# CPU_LPC1776.net
KiCad netlist of a schematic drawn in Altium Designer
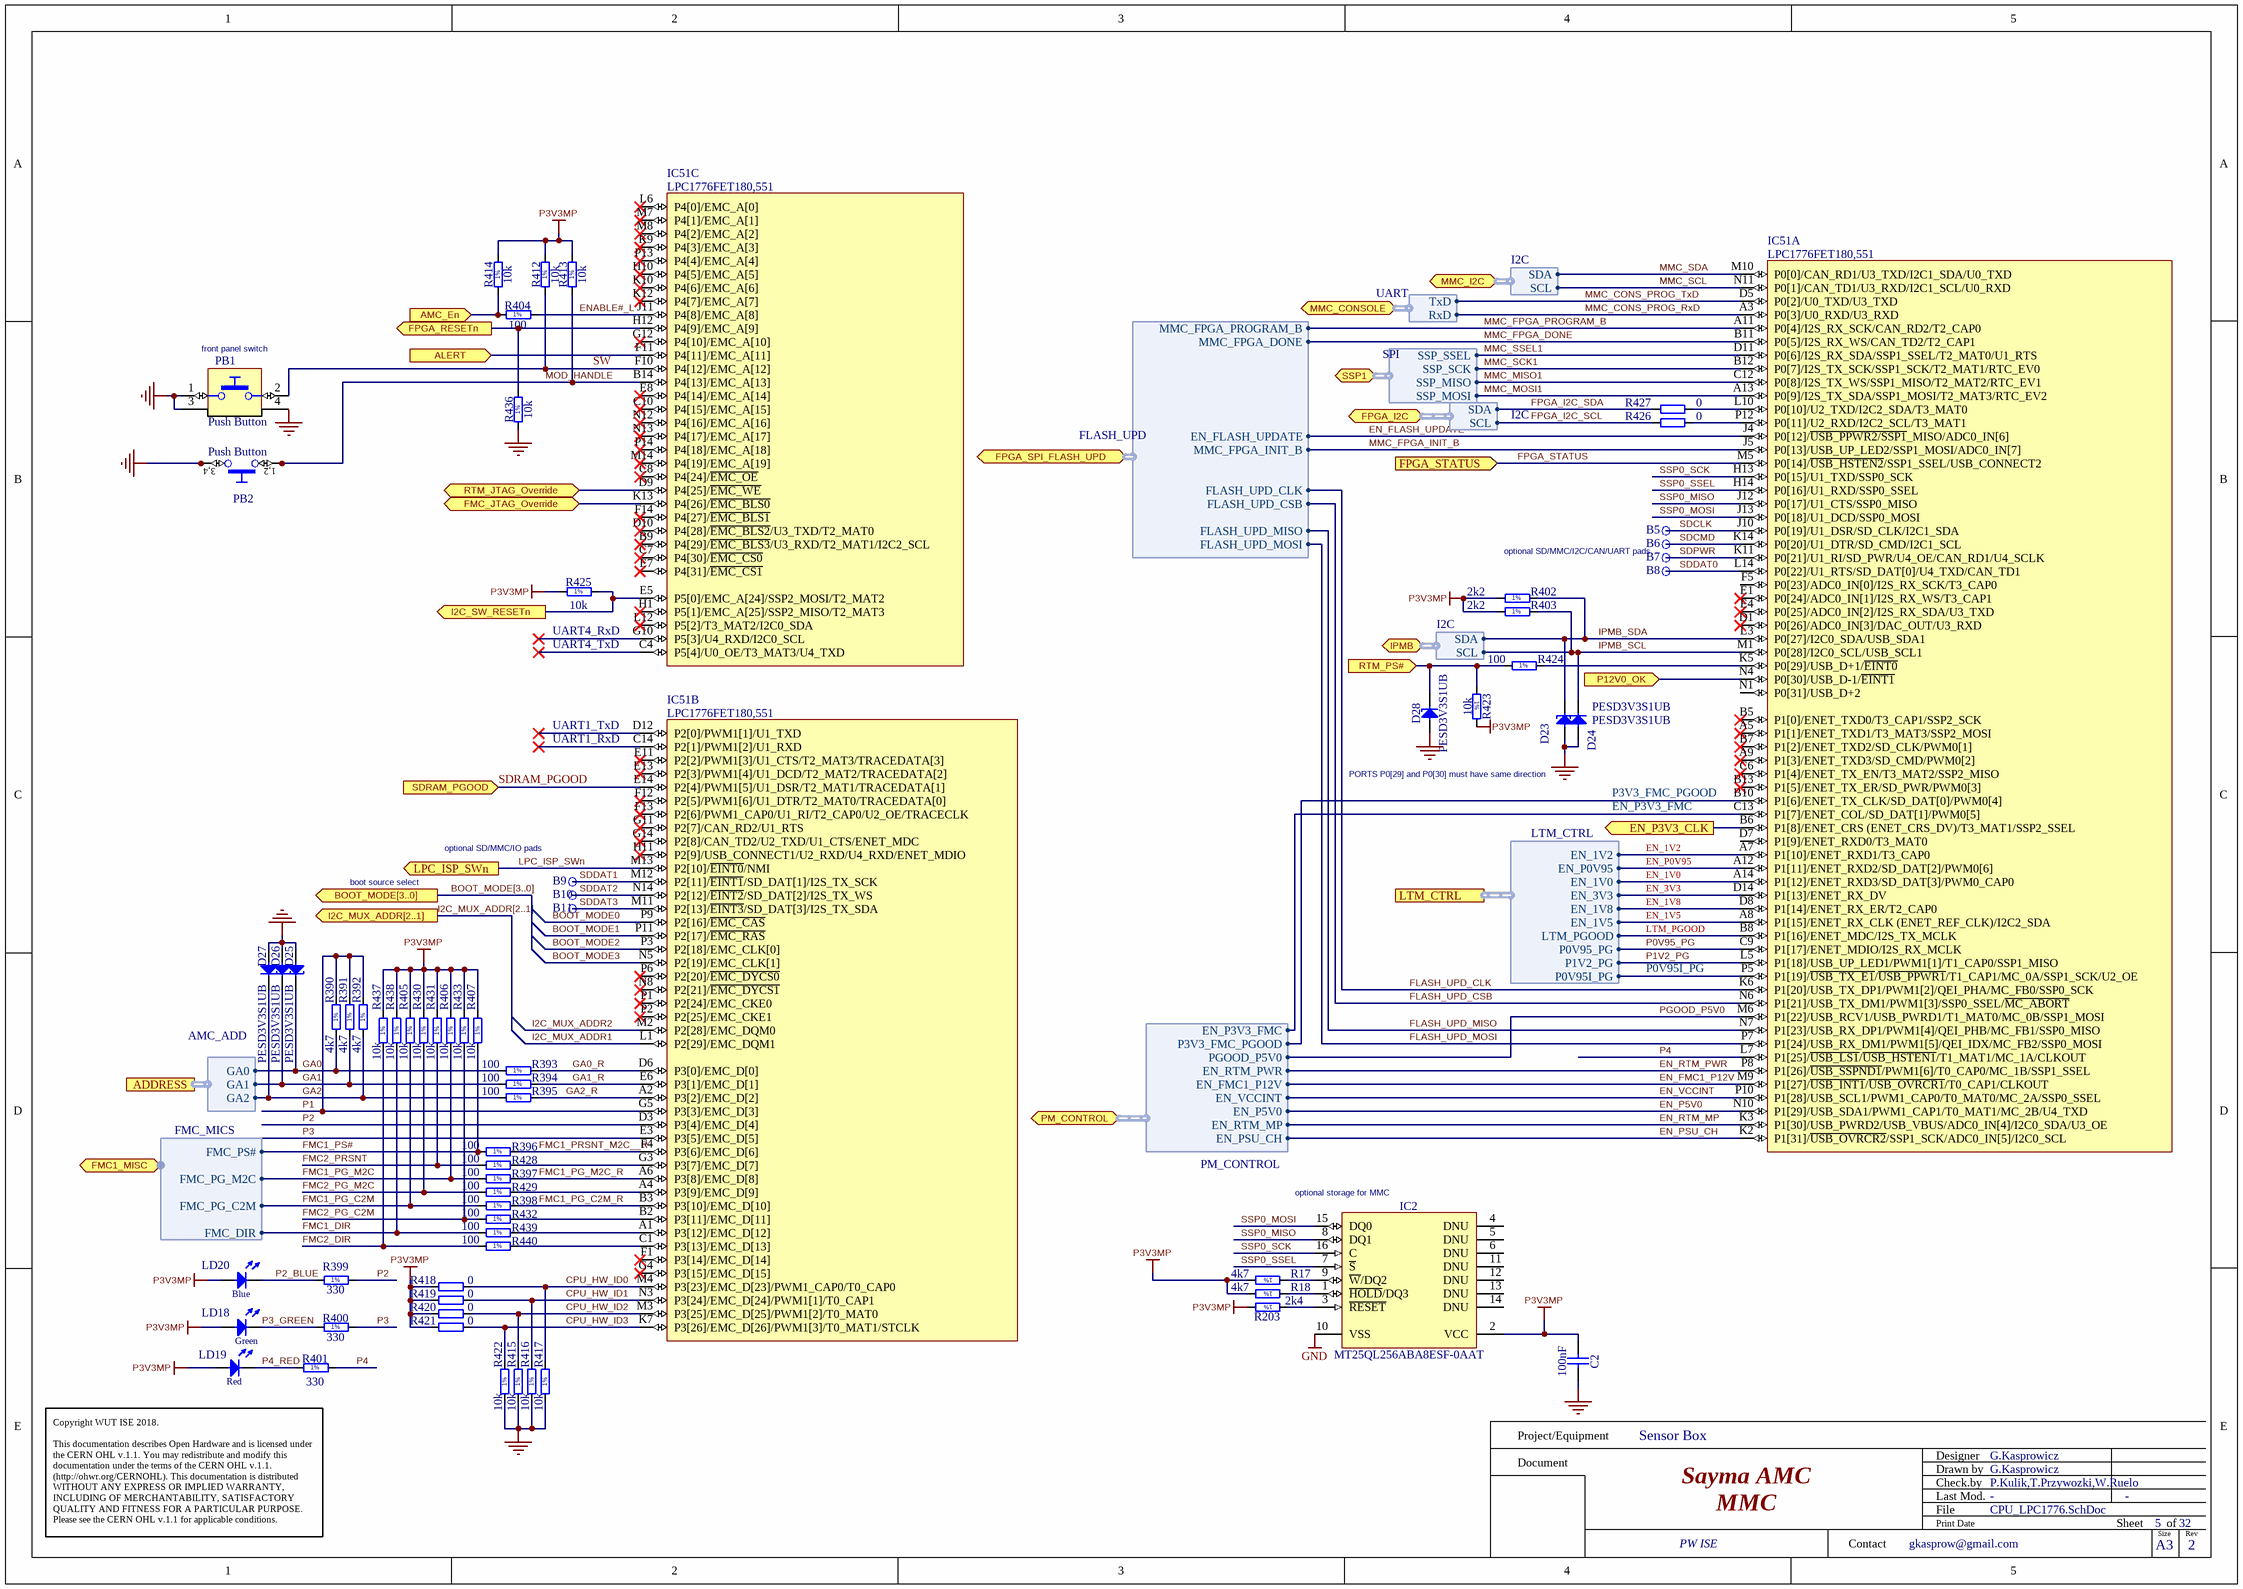
[diagram p0: CPU_LPC1776.SchDoc]

(export (version "E")
  (design (tool "Eeschema 10.0.6"))
  (components
    (comp (ref "B5")
      (value "SMD_PAD_D1MM")
      (footprint "C100")
      (libsource (lib "altium-import") (part "root_0__*"))
    )
    (comp (ref "B6")
      (value "SMD_PAD_D1MM")
      (footprint "C100")
      (libsource (lib "altium-import") (part "root_0__*"))
    )
    (comp (ref "B7")
      (value "SMD_PAD_D1MM")
      (footprint "C100")
      (libsource (lib "altium-import") (part "root_0__*"))
    )
    (comp (ref "B8")
      (value "SMD_PAD_D1MM")
      (footprint "C100")
      (libsource (lib "altium-import") (part "root_0__*"))
    )
    (comp (ref "B9")
      (value "SMD_PAD_D1MM")
      (footprint "C100")
      (libsource (lib "altium-import") (part "root_0__*"))
    )
    (comp (ref "B10")
      (value "SMD_PAD_D1MM")
      (footprint "C100")
      (libsource (lib "altium-import") (part "root_0__*"))
    )
    (comp (ref "B11")
      (value "SMD_PAD_D1MM")
      (footprint "C100")
      (libsource (lib "altium-import") (part "root_0__*"))
    )
    (comp (ref "C2")
      (value "100nF")
      (footprint "CAPC0603X33N")
      (description "Non-polarised capacitor")
      (fields
        (field (name "MANUFACTURER PART NUMBER") "CC0201_100NF_6.3V_10%_X5R")
        (field (name "MANUFACTURER") "GENERIC")
        (field (name "AUTHOR") "CERN DEM JLC")
      )
      (libsource (lib "Capacitors") (part "Capacitor - non polarized"))
    )
    (comp (ref "D23")
      (value "PESD3V3S1UB")
      (footprint "SODFL1608X65N")
      (description "ESD protection diode")
      (fields
        (field (name "MANUFACTURER") "NXP SEMICONDUCTORS")
        (field (name "VOLTAGE") "3V3")
        (field (name "AUTHOR") "CERN DEM JLC")
      )
      (libsource (lib "ICs And Semiconductors") (part "Diode ESD"))
    )
    (comp (ref "D24")
      (value "PESD3V3S1UB")
      (footprint "SODFL1608X65N")
      (description "ESD protection diode")
      (fields
        (field (name "MANUFACTURER") "NXP SEMICONDUCTORS")
        (field (name "VOLTAGE") "3V3")
        (field (name "AUTHOR") "CERN DEM JLC")
      )
      (libsource (lib "ICs And Semiconductors") (part "Diode ESD"))
    )
    (comp (ref "D25")
      (value "PESD3V3S1UB")
      (footprint "SODFL1608X65N")
      (description "ESD protection diode")
      (fields
        (field (name "MANUFACTURER") "NXP SEMICONDUCTORS")
        (field (name "VOLTAGE") "3V3")
        (field (name "AUTHOR") "CERN DEM JLC")
      )
      (libsource (lib "ICs And Semiconductors") (part "Diode ESD"))
    )
    (comp (ref "D26")
      (value "PESD3V3S1UB")
      (footprint "SODFL1608X65N")
      (description "ESD protection diode")
      (fields
        (field (name "MANUFACTURER") "NXP SEMICONDUCTORS")
        (field (name "VOLTAGE") "3V3")
        (field (name "AUTHOR") "CERN DEM JLC")
      )
      (libsource (lib "ICs And Semiconductors") (part "Diode ESD"))
    )
    (comp (ref "D27")
      (value "PESD3V3S1UB")
      (footprint "SODFL1608X65N")
      (description "ESD protection diode")
      (fields
        (field (name "MANUFACTURER") "NXP SEMICONDUCTORS")
        (field (name "VOLTAGE") "3V3")
        (field (name "AUTHOR") "CERN DEM JLC")
      )
      (libsource (lib "ICs And Semiconductors") (part "Diode ESD"))
    )
    (comp (ref "D28")
      (value "PESD3V3S1UB")
      (footprint "SODFL1608X65N")
      (description "ESD protection diode")
      (fields
        (field (name "MANUFACTURER") "NXP SEMICONDUCTORS")
        (field (name "VOLTAGE") "3V3")
        (field (name "AUTHOR") "CERN DEM JLC")
      )
      (libsource (lib "ICs And Semiconductors") (part "Diode ESD"))
    )
    (comp (ref "IC2")
      (value "MT25QL256ABA8ESF-0AAT")
      (footprint "SOIC127P1030X265-16N")
      (description "256Mbit (32MB), 2.7V-3.6V, Multiple I/O Serial NOR Flash Memory,with Reset# & Hold#")
      (fields (field (name "MANUFACTURER") "MICRON TECHNOLOGY") (field (name "AUTHOR") "CERN DEM JLC"))
      (libsource (lib "ICs And Semiconductors") (part "MT25QL256ABA8ESF"))
    )
    (comp (ref "IC51")
      (value "LPC1776FET180,551")
      (footprint "BGA180C80P14X14_1200X1200X120")
      (fields (field (name "MANUFACTURER") "NXP SEMICONDUCTORS") (field (name "AUTHOR") "CERN DEM JMW"))
      (libsource (lib "ICs And Semiconductors") (part "LPC1776FET180,551"))
    )
    (comp (ref "LD18")
      (value "Green")
      (footprint "LED_AVAGO_HSME-C120")
      (description "LED Green 1C 2A")
      (fields
        (field (name "MANUFACTURER PART NUMBER") "HSME-C120")
        (field (name "MANUFACTURER") "AVAGO TECHNOLOGIES")
        (field (name "AUTHOR") "CERN DEM JMW")
      )
      (libsource (lib "ICs And Semiconductors") (part "LED Green 1C 2A"))
    )
    (comp (ref "LD19")
      (value "Red")
      (footprint "LED_KINGBRIGHT_KPH-1608SURCK")
      (description "LED Red 1C 2A")
      (fields
        (field (name "PART NUMBER") "LED_KINGBRIGHT_KPH-1608SURCK")
        (field (name "MANUFACTURER") "KINGBRIGHT")
        (field (name "AUTHOR") "CERN DEM JLC")
      )
      (libsource (lib "ICs And Semiconductors") (part "LED Red 1C 2A"))
    )
    (comp (ref "LD20")
      (value "Blue")
      (footprint "LED_AVAGO_HSMR-C120")
      (description "LED Blue 1C 2A")
      (fields
        (field (name "MANUFACTURER PART NUMBER") "HSMR-C120")
        (field (name "MANUFACTURER") "AVAGO TECHNOLOGIES")
        (field (name "AUTHOR") "CERN DEM JLC")
      )
      (libsource (lib "ICs And Semiconductors") (part "LED Blue 1C 2A"))
    )
    (comp (ref "PB1")
      (value "Push Button")
      (footprint "PB_ALPS_SKHHLQA010")
      (description "Push-Button Switch SPDT")
      (fields
        (field (name "MANUFACTURER PART NUMBER") "SKHHLQA010")
        (field (name "MANUFACTURER") "ALPS")
        (field (name "AUTHOR") "CERN DEM JLC")
      )
      (libsource (lib "Eletro-mechanical") (part "PB SPST 1NO-2NO 34CASE"))
    )
    (comp (ref "PB2")
      (value "Push Button")
      (footprint "SW_C&K_HDT0001")
      (description "Push-Button Switch SPDT")
      (fields
        (field (name "MANUFACTURER PART NUMBER") "HDT0001")
        (field (name "MANUFACTURER") "C&K")
        (field (name "AUTHOR") "CERN DEM JLC")
      )
      (libsource (lib "Eletro-mechanical") (part "PB SPST 12NO-34NO"))
    )
    (comp (ref "R17")
      (value "4k7")
      (footprint "RESC1005X40N")
      (description "Resistor - 1%")
      (fields
        (field (name "MANUFACTURER PART NUMBER") "R0402_4K7_1%_0.0625W_100PPM")
        (field (name "MANUFACTURER") "GENERIC")
        (field (name "AUTHOR") "CERN DEM JLC")
      )
      (libsource (lib "Resistors") (part "Resistor - 1%"))
    )
    (comp (ref "R18")
      (value "4k7")
      (footprint "RESC1005X40N")
      (description "Resistor - 1%")
      (fields
        (field (name "MANUFACTURER PART NUMBER") "R0402_4K7_1%_0.0625W_100PPM")
        (field (name "MANUFACTURER") "GENERIC")
        (field (name "AUTHOR") "CERN DEM JLC")
      )
      (libsource (lib "Resistors") (part "Resistor - 1%"))
    )
    (comp (ref "R203")
      (value "2k4")
      (footprint "RESC1005X40N")
      (description "Resistor - 1%")
      (fields
        (field (name "MANUFACTURER PART NUMBER") "R0402_2K4_1%_0.0625W_100PPM")
        (field (name "MANUFACTURER") "GENERIC")
        (field (name "AUTHOR") "CERN DEM JLC")
      )
      (libsource (lib "Resistors") (part "Resistor - 1%"))
    )
    (comp (ref "R390")
      (value "4k7")
      (footprint "RESC1005X40N")
      (description "Resistor - 1%")
      (fields
        (field (name "MANUFACTURER PART NUMBER") "R0402_4K7_1%_0.0625W_100PPM")
        (field (name "MANUFACTURER") "GENERIC")
        (field (name "AUTHOR") "CERN DEM JLC")
      )
      (libsource (lib "Resistors") (part "Resistor - 1%"))
    )
    (comp (ref "R391")
      (value "4k7")
      (footprint "RESC1005X40N")
      (description "Resistor - 1%")
      (fields
        (field (name "MANUFACTURER PART NUMBER") "R0402_4K7_1%_0.0625W_100PPM")
        (field (name "MANUFACTURER") "GENERIC")
        (field (name "AUTHOR") "CERN DEM JLC")
      )
      (libsource (lib "Resistors") (part "Resistor - 1%"))
    )
    (comp (ref "R392")
      (value "4k7")
      (footprint "RESC1005X40N")
      (description "Resistor - 1%")
      (fields
        (field (name "MANUFACTURER PART NUMBER") "R0402_4K7_1%_0.0625W_100PPM")
        (field (name "MANUFACTURER") "GENERIC")
        (field (name "AUTHOR") "CERN DEM JLC")
      )
      (libsource (lib "Resistors") (part "Resistor - 1%"))
    )
    (comp (ref "R393")
      (value "100")
      (footprint "RESC1005X40N")
      (description "Resistor - 1%")
      (fields
        (field (name "MANUFACTURER PART NUMBER") "R0402_100R_1%_0.1W_100PPM_50V")
        (field (name "MANUFACTURER") "GENERIC")
        (field (name "AUTHOR") "CERN DEM JLC")
      )
      (libsource (lib "Resistors") (part "Resistor - 1%"))
    )
    (comp (ref "R394")
      (value "100")
      (footprint "RESC1005X40N")
      (description "Resistor - 1%")
      (fields
        (field (name "MANUFACTURER PART NUMBER") "R0402_100R_1%_0.1W_100PPM_50V")
        (field (name "MANUFACTURER") "GENERIC")
        (field (name "AUTHOR") "CERN DEM JLC")
      )
      (libsource (lib "Resistors") (part "Resistor - 1%"))
    )
    (comp (ref "R395")
      (value "100")
      (footprint "RESC1005X40N")
      (description "Resistor - 1%")
      (fields
        (field (name "MANUFACTURER PART NUMBER") "R0402_100R_1%_0.1W_100PPM_50V")
        (field (name "MANUFACTURER") "GENERIC")
        (field (name "AUTHOR") "CERN DEM JLC")
      )
      (libsource (lib "Resistors") (part "Resistor - 1%"))
    )
    (comp (ref "R396")
      (value "100")
      (footprint "RESC1005X40N")
      (description "Resistor - 1%")
      (fields
        (field (name "MANUFACTURER PART NUMBER") "R0402_100R_1%_0.1W_100PPM_50V")
        (field (name "MANUFACTURER") "GENERIC")
        (field (name "AUTHOR") "CERN DEM JLC")
      )
      (libsource (lib "Resistors") (part "Resistor - 1%"))
    )
    (comp (ref "R397")
      (value "100")
      (footprint "RESC1005X40N")
      (description "Resistor - 1%")
      (fields
        (field (name "MANUFACTURER PART NUMBER") "R0402_100R_1%_0.1W_100PPM_50V")
        (field (name "MANUFACTURER") "GENERIC")
        (field (name "AUTHOR") "CERN DEM JLC")
      )
      (libsource (lib "Resistors") (part "Resistor - 1%"))
    )
    (comp (ref "R398")
      (value "100")
      (footprint "RESC1005X40N")
      (description "Resistor - 1%")
      (fields
        (field (name "MANUFACTURER PART NUMBER") "R0402_100R_1%_0.1W_100PPM_50V")
        (field (name "MANUFACTURER") "GENERIC")
        (field (name "AUTHOR") "CERN DEM JLC")
      )
      (libsource (lib "Resistors") (part "Resistor - 1%"))
    )
    (comp (ref "R399")
      (value "330")
      (footprint "RESC1005X40N")
      (description "Resistor - 1%")
      (fields
        (field (name "MANUFACTURER PART NUMBER") "R0402_330R_1%_0.0625W_100PPM")
        (field (name "MANUFACTURER") "GENERIC")
        (field (name "AUTHOR") "CERN DEM JLC")
      )
      (libsource (lib "Resistors") (part "Resistor - 1%"))
    )
    (comp (ref "R400")
      (value "330")
      (footprint "RESC1005X40N")
      (description "Resistor - 1%")
      (fields
        (field (name "MANUFACTURER PART NUMBER") "R0402_330R_1%_0.0625W_100PPM")
        (field (name "MANUFACTURER") "GENERIC")
        (field (name "AUTHOR") "CERN DEM JLC")
      )
      (libsource (lib "Resistors") (part "Resistor - 1%"))
    )
    (comp (ref "R401")
      (value "330")
      (footprint "RESC1005X40N")
      (description "Resistor - 1%")
      (fields
        (field (name "MANUFACTURER PART NUMBER") "R0402_330R_1%_0.0625W_100PPM")
        (field (name "MANUFACTURER") "GENERIC")
        (field (name "AUTHOR") "CERN DEM JLC")
      )
      (libsource (lib "Resistors") (part "Resistor - 1%"))
    )
    (comp (ref "R402")
      (value "2k2")
      (footprint "RESC1005X40N")
      (description "Resistor - 1%")
      (fields
        (field (name "MANUFACTURER PART NUMBER") "R0402_2K2_1%_0.0625W_100PPM")
        (field (name "MANUFACTURER") "GENERIC")
        (field (name "AUTHOR") "CERN DEM JLC")
      )
      (libsource (lib "Resistors") (part "Resistor - 1%"))
    )
    (comp (ref "R403")
      (value "2k2")
      (footprint "RESC1005X40N")
      (description "Resistor - 1%")
      (fields
        (field (name "MANUFACTURER PART NUMBER") "R0402_2K2_1%_0.0625W_100PPM")
        (field (name "MANUFACTURER") "GENERIC")
        (field (name "AUTHOR") "CERN DEM JLC")
      )
      (libsource (lib "Resistors") (part "Resistor - 1%"))
    )
    (comp (ref "R404")
      (value "100")
      (footprint "RESC1005X40N")
      (description "Resistor - 1%")
      (fields
        (field (name "MANUFACTURER PART NUMBER") "R0402_100R_1%_0.1W_100PPM_50V")
        (field (name "MANUFACTURER") "GENERIC")
        (field (name "AUTHOR") "CERN DEM JLC")
      )
      (libsource (lib "Resistors") (part "Resistor - 1%"))
    )
    (comp (ref "R405")
      (value "10k")
      (footprint "RESC1005X40N")
      (description "Resistor - 1%")
      (fields
        (field (name "MANUFACTURER PART NUMBER") "R0402_10K_1%_0.0625W_100PPM")
        (field (name "MANUFACTURER") "GENERIC")
        (field (name "AUTHOR") "CERN DEM JLC")
      )
      (libsource (lib "Resistors") (part "Resistor - 1%"))
    )
    (comp (ref "R406")
      (value "10k")
      (footprint "RESC1005X40N")
      (description "Resistor - 1%")
      (fields
        (field (name "MANUFACTURER PART NUMBER") "R0402_10K_1%_0.0625W_100PPM")
        (field (name "MANUFACTURER") "GENERIC")
        (field (name "AUTHOR") "CERN DEM JLC")
      )
      (libsource (lib "Resistors") (part "Resistor - 1%"))
    )
    (comp (ref "R407")
      (value "10k")
      (footprint "RESC1005X40N")
      (description "Resistor - 1%")
      (fields
        (field (name "MANUFACTURER PART NUMBER") "R0402_10K_1%_0.0625W_100PPM")
        (field (name "MANUFACTURER") "GENERIC")
        (field (name "AUTHOR") "CERN DEM JLC")
      )
      (libsource (lib "Resistors") (part "Resistor - 1%"))
    )
    (comp (ref "R412")
      (value "10k")
      (footprint "RESC1005X40N")
      (description "Resistor - 1%")
      (fields
        (field (name "MANUFACTURER PART NUMBER") "R0402_10K_1%_0.0625W_100PPM")
        (field (name "MANUFACTURER") "GENERIC")
        (field (name "AUTHOR") "CERN DEM JLC")
      )
      (libsource (lib "Resistors") (part "Resistor - 1%"))
    )
    (comp (ref "R413")
      (value "10k")
      (footprint "RESC1005X40N")
      (description "Resistor - 1%")
      (fields
        (field (name "MANUFACTURER PART NUMBER") "R0402_10K_1%_0.0625W_100PPM")
        (field (name "MANUFACTURER") "GENERIC")
        (field (name "AUTHOR") "CERN DEM JLC")
      )
      (libsource (lib "Resistors") (part "Resistor - 1%"))
    )
    (comp (ref "R414")
      (value "10k")
      (footprint "RESC1005X40N")
      (description "Resistor - 1%")
      (fields
        (field (name "MANUFACTURER PART NUMBER") "R0402_10K_1%_0.0625W_100PPM")
        (field (name "MANUFACTURER") "GENERIC")
        (field (name "AUTHOR") "CERN DEM JLC")
      )
      (libsource (lib "Resistors") (part "Resistor - 1%"))
    )
    (comp (ref "R415")
      (value "10k")
      (footprint "RESC1005X40N")
      (description "Resistor - 1%")
      (fields
        (field (name "MANUFACTURER PART NUMBER") "R0402_10K_1%_0.0625W_100PPM")
        (field (name "MANUFACTURER") "GENERIC")
        (field (name "AUTHOR") "CERN DEM JLC")
      )
      (libsource (lib "Resistors") (part "Resistor - 1%"))
    )
    (comp (ref "R416")
      (value "10k")
      (footprint "RESC1005X40N")
      (description "Resistor - 1%")
      (fields
        (field (name "MANUFACTURER PART NUMBER") "R0402_10K_1%_0.0625W_100PPM")
        (field (name "MANUFACTURER") "GENERIC")
        (field (name "AUTHOR") "CERN DEM JLC")
      )
      (libsource (lib "Resistors") (part "Resistor - 1%"))
    )
    (comp (ref "R417")
      (value "10k")
      (footprint "RESC1005X40N")
      (description "Resistor - 1%")
      (fields
        (field (name "MANUFACTURER PART NUMBER") "R0402_10K_1%_0.0625W_100PPM")
        (field (name "MANUFACTURER") "GENERIC")
        (field (name "AUTHOR") "CERN DEM JLC")
      )
      (libsource (lib "Resistors") (part "Resistor - 1%"))
    )
    (comp (ref "R418")
      (value "0")
      (footprint "RESC1005X40N")
      (description "Resistor")
      (fields
        (field (name "MANUFACTURER PART NUMBER") "R0402_0R_JUMPER")
        (field (name "MANUFACTURER") "GENERIC")
        (field (name "AUTHOR") "CERN DEM JLC")
      )
      (libsource (lib "Resistors") (part "Resistor"))
    )
    (comp (ref "R419")
      (value "0")
      (footprint "RESC1005X40N")
      (description "Resistor")
      (fields
        (field (name "MANUFACTURER PART NUMBER") "R0402_0R_JUMPER")
        (field (name "MANUFACTURER") "GENERIC")
        (field (name "AUTHOR") "CERN DEM JLC")
      )
      (libsource (lib "Resistors") (part "Resistor"))
    )
    (comp (ref "R420")
      (value "0")
      (footprint "RESC1005X40N")
      (description "Resistor")
      (fields
        (field (name "MANUFACTURER PART NUMBER") "R0402_0R_JUMPER")
        (field (name "MANUFACTURER") "GENERIC")
        (field (name "AUTHOR") "CERN DEM JLC")
      )
      (libsource (lib "Resistors") (part "Resistor"))
    )
    (comp (ref "R421")
      (value "0")
      (footprint "RESC1005X40N")
      (description "Resistor")
      (fields
        (field (name "MANUFACTURER PART NUMBER") "R0402_0R_JUMPER")
        (field (name "MANUFACTURER") "GENERIC")
        (field (name "AUTHOR") "CERN DEM JLC")
      )
      (libsource (lib "Resistors") (part "Resistor"))
    )
    (comp (ref "R422")
      (value "10k")
      (footprint "RESC1005X40N")
      (description "Resistor - 1%")
      (fields
        (field (name "MANUFACTURER PART NUMBER") "R0402_10K_1%_0.0625W_100PPM")
        (field (name "MANUFACTURER") "GENERIC")
        (field (name "AUTHOR") "CERN DEM JLC")
      )
      (libsource (lib "Resistors") (part "Resistor - 1%"))
    )
    (comp (ref "R423")
      (value "10k")
      (footprint "RESC1005X40N")
      (description "Resistor - 1%")
      (fields
        (field (name "MANUFACTURER PART NUMBER") "R0402_10K_1%_0.0625W_100PPM")
        (field (name "MANUFACTURER") "GENERIC")
        (field (name "AUTHOR") "CERN DEM JLC")
      )
      (libsource (lib "Resistors") (part "Resistor - 1%"))
    )
    (comp (ref "R424")
      (value "100")
      (footprint "RESC1005X40N")
      (description "Resistor - 1%")
      (fields
        (field (name "MANUFACTURER PART NUMBER") "R0402_100R_1%_0.1W_100PPM_50V")
        (field (name "MANUFACTURER") "GENERIC")
        (field (name "AUTHOR") "CERN DEM JLC")
      )
      (libsource (lib "Resistors") (part "Resistor - 1%"))
    )
    (comp (ref "R425")
      (value "10k")
      (footprint "RESC1005X40N")
      (description "Resistor - 1%")
      (fields
        (field (name "MANUFACTURER PART NUMBER") "R0402_10K_1%_0.0625W_100PPM")
        (field (name "MANUFACTURER") "GENERIC")
        (field (name "AUTHOR") "CERN DEM JLC")
      )
      (libsource (lib "Resistors") (part "Resistor - 1%"))
    )
    (comp (ref "R426")
      (value "0")
      (footprint "RESC1005X40N")
      (description "Resistor")
      (fields
        (field (name "MANUFACTURER PART NUMBER") "R0402_0R_JUMPER")
        (field (name "MANUFACTURER") "GENERIC")
        (field (name "AUTHOR") "CERN DEM JLC")
      )
      (libsource (lib "Resistors") (part "Resistor"))
    )
    (comp (ref "R427")
      (value "0")
      (footprint "RESC1005X40N")
      (description "Resistor")
      (fields
        (field (name "MANUFACTURER PART NUMBER") "R0402_0R_JUMPER")
        (field (name "MANUFACTURER") "GENERIC")
        (field (name "AUTHOR") "CERN DEM JLC")
      )
      (libsource (lib "Resistors") (part "Resistor"))
    )
    (comp (ref "R428")
      (value "100")
      (footprint "RESC1005X40N")
      (description "Resistor - 1%")
      (fields
        (field (name "MANUFACTURER PART NUMBER") "R0402_100R_1%_0.1W_100PPM_50V")
        (field (name "MANUFACTURER") "GENERIC")
        (field (name "AUTHOR") "CERN DEM JLC")
      )
      (libsource (lib "Resistors") (part "Resistor - 1%"))
    )
    (comp (ref "R429")
      (value "100")
      (footprint "RESC1005X40N")
      (description "Resistor - 1%")
      (fields
        (field (name "MANUFACTURER PART NUMBER") "R0402_100R_1%_0.1W_100PPM_50V")
        (field (name "MANUFACTURER") "GENERIC")
        (field (name "AUTHOR") "CERN DEM JLC")
      )
      (libsource (lib "Resistors") (part "Resistor - 1%"))
    )
    (comp (ref "R430")
      (value "10k")
      (footprint "RESC1005X40N")
      (description "Resistor - 1%")
      (fields
        (field (name "MANUFACTURER PART NUMBER") "R0402_10K_1%_0.0625W_100PPM")
        (field (name "MANUFACTURER") "GENERIC")
        (field (name "AUTHOR") "CERN DEM JLC")
      )
      (libsource (lib "Resistors") (part "Resistor - 1%"))
    )
    (comp (ref "R431")
      (value "10k")
      (footprint "RESC1005X40N")
      (description "Resistor - 1%")
      (fields
        (field (name "MANUFACTURER PART NUMBER") "R0402_10K_1%_0.0625W_100PPM")
        (field (name "MANUFACTURER") "GENERIC")
        (field (name "AUTHOR") "CERN DEM JLC")
      )
      (libsource (lib "Resistors") (part "Resistor - 1%"))
    )
    (comp (ref "R432")
      (value "100")
      (footprint "RESC1005X40N")
      (description "Resistor - 1%")
      (fields
        (field (name "MANUFACTURER PART NUMBER") "R0402_100R_1%_0.1W_100PPM_50V")
        (field (name "MANUFACTURER") "GENERIC")
        (field (name "AUTHOR") "CERN DEM JLC")
      )
      (libsource (lib "Resistors") (part "Resistor - 1%"))
    )
    (comp (ref "R433")
      (value "10k")
      (footprint "RESC1005X40N")
      (description "Resistor - 1%")
      (fields
        (field (name "MANUFACTURER PART NUMBER") "R0402_10K_1%_0.0625W_100PPM")
        (field (name "MANUFACTURER") "GENERIC")
        (field (name "AUTHOR") "CERN DEM JLC")
      )
      (libsource (lib "Resistors") (part "Resistor - 1%"))
    )
    (comp (ref "R436")
      (value "10k")
      (footprint "RESC1005X40N")
      (description "Resistor - 1%")
      (fields
        (field (name "MANUFACTURER PART NUMBER") "R0402_10K_1%_0.0625W_100PPM")
        (field (name "MANUFACTURER") "GENERIC")
        (field (name "AUTHOR") "CERN DEM JLC")
      )
      (libsource (lib "Resistors") (part "Resistor - 1%"))
    )
    (comp (ref "R437")
      (value "10k")
      (footprint "RESC1005X40N")
      (description "Resistor - 1%")
      (fields
        (field (name "MANUFACTURER PART NUMBER") "R0402_10K_1%_0.0625W_100PPM")
        (field (name "MANUFACTURER") "GENERIC")
        (field (name "AUTHOR") "CERN DEM JLC")
      )
      (libsource (lib "Resistors") (part "Resistor - 1%"))
    )
    (comp (ref "R438")
      (value "10k")
      (footprint "RESC1005X40N")
      (description "Resistor - 1%")
      (fields
        (field (name "MANUFACTURER PART NUMBER") "R0402_10K_1%_0.0625W_100PPM")
        (field (name "MANUFACTURER") "GENERIC")
        (field (name "AUTHOR") "CERN DEM JLC")
      )
      (libsource (lib "Resistors") (part "Resistor - 1%"))
    )
    (comp (ref "R439")
      (value "100")
      (footprint "RESC1005X40N")
      (description "Resistor - 1%")
      (fields
        (field (name "MANUFACTURER PART NUMBER") "R0402_100R_1%_0.1W_100PPM_50V")
        (field (name "MANUFACTURER") "GENERIC")
        (field (name "AUTHOR") "CERN DEM JLC")
      )
      (libsource (lib "Resistors") (part "Resistor - 1%"))
    )
    (comp (ref "R440")
      (value "100")
      (footprint "RESC1005X40N")
      (description "Resistor - 1%")
      (fields
        (field (name "MANUFACTURER PART NUMBER") "R0402_100R_1%_0.1W_100PPM_50V")
        (field (name "MANUFACTURER") "GENERIC")
        (field (name "AUTHOR") "CERN DEM JLC")
      )
      (libsource (lib "Resistors") (part "Resistor - 1%"))
    )
  )
  (nets
    (net (code "9") (name "/ALERT") (class "Default")
      (node (ref "IC51") (pin "F11") (pinfunction "P4[11]/EMC_A[11]_F11") (pintype "bidirectional"))
    )
    (net (code "10") (name "/AMC_En") (class "Default")
      (node (ref "R404") (pin "1") (pinfunction "1_1") (pintype "passive"))
      (node (ref "R414") (pin "1") (pinfunction "1_1") (pintype "passive"))
    )
    (net (code "11") (name "/BOOT_MODE0") (class "Default")
      (node (ref "IC51") (pin "P9") (pinfunction "P2[16]/~{EMC_CAS}_P9") (pintype "bidirectional"))
    )
    (net (code "12") (name "/BOOT_MODE1") (class "Default")
      (node (ref "IC51") (pin "P11") (pinfunction "P2[17]/~{EMC_RAS}_P11") (pintype "bidirectional"))
    )
    (net (code "13") (name "/BOOT_MODE2") (class "Default")
      (node (ref "IC51") (pin "P3") (pinfunction "P2[18]/EMC_CLK[0]_P3") (pintype "bidirectional"))
    )
    (net (code "14") (name "/BOOT_MODE3") (class "Default")
      (node (ref "IC51") (pin "N5") (pinfunction "P2[19]/EMC_CLK[1]_N5") (pintype "bidirectional"))
    )
    (net (code "16") (name "/CPU_HW_ID0") (class "Default")
      (node (ref "IC51") (pin "M4") (pinfunction "P3[23]/EMC_D[23]/PWM1_CAP0/T0_CAP0_M4") (pintype "bidirectional"))
      (node (ref "R417") (pin "2") (pinfunction "2_2") (pintype "passive"))
      (node (ref "R418") (pin "2") (pinfunction "2_2") (pintype "passive"))
    )
    (net (code "17") (name "/CPU_HW_ID1") (class "Default")
      (node (ref "IC51") (pin "N3") (pinfunction "P3[24]/EMC_D[24]/PWM1[1]/T0_CAP1_N3") (pintype "bidirectional"))
      (node (ref "R416") (pin "2") (pinfunction "2_2") (pintype "passive"))
      (node (ref "R419") (pin "2") (pinfunction "2_2") (pintype "passive"))
    )
    (net (code "18") (name "/CPU_HW_ID2") (class "Default")
      (node (ref "IC51") (pin "M3") (pinfunction "P3[25]/EMC_D[25]/PWM1[2]/T0_MAT0_M3") (pintype "bidirectional"))
      (node (ref "R415") (pin "2") (pinfunction "2_2") (pintype "passive"))
      (node (ref "R420") (pin "2") (pinfunction "2_2") (pintype "passive"))
    )
    (net (code "19") (name "/CPU_HW_ID3") (class "Default")
      (node (ref "IC51") (pin "K7") (pinfunction "P3[26]/EMC_D[26]/PWM1[3]/T0_MAT1/STCLK_K7") (pintype "bidirectional"))
      (node (ref "R421") (pin "2") (pinfunction "2_2") (pintype "passive"))
      (node (ref "R422") (pin "2") (pinfunction "2_2") (pintype "passive"))
    )
    (net (code "20") (name "/ENABLE#_L") (class "Default")
      (node (ref "IC51") (pin "J11") (pinfunction "P4[8]/EMC_A[8]_J11") (pintype "bidirectional"))
      (node (ref "R404") (pin "2") (pinfunction "2_2") (pintype "passive"))
    )
    (net (code "21") (name "/EN_1V0") (class "Default")
      (node (ref "IC51") (pin "A14") (pinfunction "P1[12]/ENET_RXD3/SD_DAT[3]/PWM0_CAP0_A14") (pintype "bidirectional"))
    )
    (net (code "22") (name "/EN_1V2") (class "Default")
      (node (ref "IC51") (pin "A7") (pinfunction "P1[10]/ENET_RXD1/T3_CAP0_A7") (pintype "bidirectional"))
    )
    (net (code "23") (name "/EN_1V5") (class "Default")
      (node (ref "IC51") (pin "A8") (pinfunction "P1[15]/ENET_RX_CLK_(ENET_REF_CLK)/I2C2_SDA_A8") (pintype "bidirectional"))
    )
    (net (code "24") (name "/EN_1V8") (class "Default")
      (node (ref "IC51") (pin "D8") (pinfunction "P1[14]/ENET_RX_ER/T2_CAP0_D8") (pintype "bidirectional"))
    )
    (net (code "25") (name "/EN_3V3") (class "Default")
      (node (ref "IC51") (pin "D14") (pinfunction "P1[13]/ENET_RX_DV_D14") (pintype "bidirectional"))
    )
    (net (code "26") (name "/EN_FLASH_UPDATE") (class "Default")
      (node (ref "IC51") (pin "J4") (pinfunction "P0[12]/~{USB_PPWR2/SSP1}_MISO/ADC0_IN[6]_J4") (pintype "bidirectional"))
    )
    (net (code "27") (name "/EN_FMC1_P12V") (class "Default")
      (node (ref "IC51") (pin "M9") (pinfunction "P1[27]/~{USB_INT1}/~{USB_OVRCR1}/T0_CAP1/CLKOUT_M9") (pintype "bidirectional"))
    )
    (net (code "28") (name "/EN_P0V95") (class "Default")
      (node (ref "IC51") (pin "A12") (pinfunction "P1[11]/ENET_RXD2/SD_DAT[2]/PWM0[6]_A12") (pintype "bidirectional"))
    )
    (net (code "29") (name "/EN_P3V3_CLK") (class "Default")
      (node (ref "IC51") (pin "B6") (pinfunction "P1[8]/ENET_CRS_(ENET_CRS_DV)/T3_MAT1/SSP2_SSEL_B6") (pintype "bidirectional"))
    )
    (net (code "30") (name "/EN_P3V3_FMC") (class "Default")
      (node (ref "IC51") (pin "C13") (pinfunction "P1[7]/ENET_COL/SD_DAT[1]/PWM0[5]_C13") (pintype "bidirectional"))
    )
    (net (code "31") (name "/EN_P5V0") (class "Default")
      (node (ref "IC51") (pin "N10") (pinfunction "P1[29]/USB_SDA1/PWM1_CAP1/T0_MAT1/MC_2B/U4_TXD_N10") (pintype "bidirectional"))
    )
    (net (code "32") (name "/EN_PSU_CH") (class "Default")
      (node (ref "IC51") (pin "K2") (pinfunction "P1[31]/~{USB_OVRCR2}/SSP1_SCK/ADC0_IN[5]/I2C0_SCL_K2") (pintype "bidirectional"))
    )
    (net (code "33") (name "/EN_RTM_MP") (class "Default")
      (node (ref "IC51") (pin "K3") (pinfunction "P1[30]/USB_PWRD2/USB_VBUS/ADC0_IN[4]/I2C0_SDA/U3_OE_K3") (pintype "bidirectional"))
    )
    (net (code "34") (name "/EN_RTM_PWR") (class "Default")
      (node (ref "IC51") (pin "P8") (pinfunction "P1[26]/~{USB_SSPND1}/PWM1[6]/T0_CAP0/MC_1B/SSP1_SSEL_P8") (pintype "bidirectional"))
    )
    (net (code "35") (name "/EN_VCCINT") (class "Default")
      (node (ref "IC51") (pin "P10") (pinfunction "P1[28]/USB_SCL1/PWM1_CAP0/T0_MAT0/MC_2A/SSP0_SSEL_P10") (pintype "bidirectional"))
    )
    (net (code "36") (name "/FLASH_UPD_CLK") (class "Default")
      (node (ref "IC51") (pin "K6") (pinfunction "P1[20]/USB_TX_DP1/PWM1[2]/QEI_PHA/MC_FB0/SSP0_SCK_K6") (pintype "bidirectional"))
    )
    (net (code "37") (name "/FLASH_UPD_CSB") (class "Default")
      (node (ref "IC51") (pin "N6") (pinfunction "P1[21]/USB_TX_DM1/PWM1[3]/SSP0_SSEL/~{MC_ABORT}_N6") (pintype "bidirectional"))
    )
    (net (code "38") (name "/FLASH_UPD_MISO") (class "Default")
      (node (ref "IC51") (pin "N7") (pinfunction "P1[23]/USB_RX_DP1/PWM1[4]/QEI_PHB/MC_FB1/SSP0_MISO_N7") (pintype "bidirectional"))
    )
    (net (code "39") (name "/FLASH_UPD_MOSI") (class "Default")
      (node (ref "IC51") (pin "P7") (pinfunction "P1[24]/USB_RX_DM1/PWM1[5]/QEI_IDX/MC_FB2/SSP0_MOSI_P7") (pintype "bidirectional"))
    )
    (net (code "40") (name "/FMC1_DIR") (class "Default")
      (node (ref "R438") (pin "1") (pinfunction "1_1") (pintype "passive"))
      (node (ref "R439") (pin "1") (pinfunction "1_1") (pintype "passive"))
    )
    (net (code "41") (name "/FMC1_PG_C2M") (class "Default")
      (node (ref "R398") (pin "1") (pinfunction "1_1") (pintype "passive"))
      (node (ref "R405") (pin "1") (pinfunction "1_1") (pintype "passive"))
    )
    (net (code "42") (name "/FMC1_PG_C2M_R") (class "Default")
      (node (ref "IC51") (pin "B3") (pinfunction "P3[10]/EMC_D[10]_B3") (pintype "bidirectional"))
      (node (ref "R398") (pin "2") (pinfunction "2_2") (pintype "passive"))
    )
    (net (code "43") (name "/FMC1_PG_M2C") (class "Default")
      (node (ref "R397") (pin "1") (pinfunction "1_1") (pintype "passive"))
      (node (ref "R406") (pin "1") (pinfunction "1_1") (pintype "passive"))
    )
    (net (code "44") (name "/FMC1_PG_M2C_R") (class "Default")
      (node (ref "IC51") (pin "A6") (pinfunction "P3[8]/EMC_D[8]_A6") (pintype "bidirectional"))
      (node (ref "R397") (pin "2") (pinfunction "2_2") (pintype "passive"))
    )
    (net (code "45") (name "/FMC1_PRSNT_M2C__R") (class "Default")
      (node (ref "IC51") (pin "F4") (pinfunction "P3[6]/EMC_D[6]_F4") (pintype "bidirectional"))
      (node (ref "R396") (pin "2") (pinfunction "2_2") (pintype "passive"))
    )
    (net (code "46") (name "/FMC1_PS#") (class "Default")
      (node (ref "R396") (pin "1") (pinfunction "1_1") (pintype "passive"))
      (node (ref "R407") (pin "1") (pinfunction "1_1") (pintype "passive"))
    )
    (net (code "47") (name "/FMC2_DIR") (class "Default")
      (node (ref "R437") (pin "1") (pinfunction "1_1") (pintype "passive"))
      (node (ref "R440") (pin "1") (pinfunction "1_1") (pintype "passive"))
    )
    (net (code "48") (name "/FMC2_PG_C2M") (class "Default")
      (node (ref "R432") (pin "1") (pinfunction "1_1") (pintype "passive"))
      (node (ref "R433") (pin "1") (pinfunction "1_1") (pintype "passive"))
    )
    (net (code "49") (name "/FMC2_PG_M2C") (class "Default")
      (node (ref "R429") (pin "1") (pinfunction "1_1") (pintype "passive"))
      (node (ref "R430") (pin "1") (pinfunction "1_1") (pintype "passive"))
    )
    (net (code "50") (name "/FMC2_PRSNT") (class "Default")
      (node (ref "R428") (pin "1") (pinfunction "1_1") (pintype "passive"))
      (node (ref "R431") (pin "1") (pinfunction "1_1") (pintype "passive"))
    )
    (net (code "51") (name "/FMC_JTAG_Override") (class "Default")
      (node (ref "IC51") (pin "K13") (pinfunction "P4[26]/~{EMC_BLS0}_K13") (pintype "bidirectional"))
    )
    (net (code "52") (name "/FPGA_I2C_SCL") (class "Default")
      (node (ref "R426") (pin "1") (pinfunction "1_1") (pintype "passive"))
    )
    (net (code "53") (name "/FPGA_I2C_SDA") (class "Default")
      (node (ref "R427") (pin "1") (pinfunction "1_1") (pintype "passive"))
    )
    (net (code "54") (name "/FPGA_RESETn") (class "Default")
      (node (ref "IC51") (pin "H12") (pinfunction "P4[9]/EMC_A[9]_H12") (pintype "bidirectional"))
      (node (ref "R436") (pin "2") (pinfunction "2_2") (pintype "passive"))
    )
    (net (code "55") (name "/FPGA_STATUS") (class "Default")
      (node (ref "IC51") (pin "M5") (pinfunction "P0[14]/~{USB_HSTEN2}/SSP1_SSEL/USB_CONNECT2_M5") (pintype "bidirectional"))
    )
    (net (code "56") (name "/GA0") (class "Default")
      (node (ref "D25") (pin "1") (pinfunction "C_1") (pintype "passive"))
      (node (ref "R390") (pin "1") (pinfunction "1_1") (pintype "passive"))
      (node (ref "R393") (pin "1") (pinfunction "1_1") (pintype "passive"))
    )
    (net (code "57") (name "/GA0_R") (class "Default")
      (node (ref "IC51") (pin "D6") (pinfunction "P3[0]/EMC_D[0]_D6") (pintype "bidirectional"))
      (node (ref "R393") (pin "2") (pinfunction "2_2") (pintype "passive"))
    )
    (net (code "58") (name "/GA1") (class "Default")
      (node (ref "D26") (pin "1") (pinfunction "C_1") (pintype "passive"))
      (node (ref "R391") (pin "1") (pinfunction "1_1") (pintype "passive"))
      (node (ref "R394") (pin "1") (pinfunction "1_1") (pintype "passive"))
    )
    (net (code "59") (name "/GA1_R") (class "Default")
      (node (ref "IC51") (pin "E6") (pinfunction "P3[1]/EMC_D[1]_E6") (pintype "bidirectional"))
      (node (ref "R394") (pin "2") (pinfunction "2_2") (pintype "passive"))
    )
    (net (code "60") (name "/GA2") (class "Default")
      (node (ref "D27") (pin "1") (pinfunction "C_1") (pintype "passive"))
      (node (ref "R392") (pin "1") (pinfunction "1_1") (pintype "passive"))
      (node (ref "R395") (pin "1") (pinfunction "1_1") (pintype "passive"))
    )
    (net (code "61") (name "/GA2_R") (class "Default")
      (node (ref "IC51") (pin "A2") (pinfunction "P3[2]/EMC_D[2]_A2") (pintype "bidirectional"))
      (node (ref "R395") (pin "2") (pinfunction "2_2") (pintype "passive"))
    )
    (net (code "62") (name "/I2C_MUX_ADDR1") (class "Default")
      (node (ref "IC51") (pin "L1") (pinfunction "P2[29]/EMC_DQM1_L1") (pintype "bidirectional"))
    )
    (net (code "63") (name "/I2C_MUX_ADDR2") (class "Default")
      (node (ref "IC51") (pin "M2") (pinfunction "P2[28]/EMC_DQM0_M2") (pintype "bidirectional"))
    )
    (net (code "65") (name "/I2C_SW_RESETn") (class "Default")
      (node (ref "IC51") (pin "E5") (pinfunction "P5[0]/EMC_A[24]/SSP2_MOSI/T2_MAT2_E5") (pintype "bidirectional"))
      (node (ref "R425") (pin "2") (pinfunction "2_2") (pintype "passive"))
    )
    (net (code "66") (name "/IPMB_SCL") (class "Default")
      (node (ref "D24") (pin "1") (pinfunction "C_1") (pintype "passive"))
      (node (ref "IC51") (pin "M1") (pinfunction "P0[28]/I2C0_SCL/USB_SCL1_M1") (pintype "bidirectional"))
      (node (ref "R403") (pin "2") (pinfunction "2_2") (pintype "passive"))
    )
    (net (code "67") (name "/IPMB_SDA") (class "Default")
      (node (ref "D23") (pin "1") (pinfunction "C_1") (pintype "passive"))
      (node (ref "IC51") (pin "L3") (pinfunction "P0[27]/I2C0_SDA/USB_SDA1_L3") (pintype "bidirectional"))
      (node (ref "R402") (pin "2") (pinfunction "2_2") (pintype "passive"))
    )
    (net (code "68") (name "/LPC_ISP_SWn") (class "Default")
      (node (ref "IC51") (pin "M13") (pinfunction "P2[10]/~{EINT0}/NMI_M13") (pintype "bidirectional"))
    )
    (net (code "69") (name "/LTM_PGOOD") (class "Default")
      (node (ref "IC51") (pin "B8") (pinfunction "P1[16]/ENET_MDC/I2S_TX_MCLK_B8") (pintype "bidirectional"))
    )
    (net (code "70") (name "/MMC_CONS_PROG_RxD") (class "Default")
      (node (ref "IC51") (pin "A3") (pinfunction "P0[3]/U0_RXD/U3_RXD_A3") (pintype "bidirectional"))
    )
    (net (code "71") (name "/MMC_CONS_PROG_TxD") (class "Default")
      (node (ref "IC51") (pin "D5") (pinfunction "P0[2]/U0_TXD/U3_TXD_D5") (pintype "bidirectional"))
    )
    (net (code "72") (name "/MMC_FPGA_DONE") (class "Default")
      (node (ref "IC51") (pin "B11") (pinfunction "P0[5]/I2S_RX_WS/CAN_TD2/T2_CAP1_B11") (pintype "bidirectional"))
    )
    (net (code "73") (name "/MMC_FPGA_INIT_B") (class "Default")
      (node (ref "IC51") (pin "J5") (pinfunction "P0[13]/USB_UP_LED2/SSP1_MOSI/ADC0_IN[7]_J5") (pintype "bidirectional"))
    )
    (net (code "74") (name "/MMC_FPGA_PROGRAM_B") (class "Default")
      (node (ref "IC51") (pin "A11") (pinfunction "P0[4]/I2S_RX_SCK/CAN_RD2/T2_CAP0_A11") (pintype "bidirectional"))
    )
    (net (code "75") (name "/MMC_MISO1") (class "Default")
      (node (ref "IC51") (pin "C12") (pinfunction "P0[8]/I2S_TX_WS/SSP1_MISO/T2_MAT2/RTC_EV1_C12") (pintype "bidirectional"))
    )
    (net (code "76") (name "/MMC_SCK1") (class "Default")
      (node (ref "IC51") (pin "B12") (pinfunction "P0[7]/I2S_TX_SCK/SSP1_SCK/T2_MAT1/RTC_EV0_B12") (pintype "bidirectional"))
    )
    (net (code "77") (name "/MMC_SCL") (class "Default")
      (node (ref "IC51") (pin "N11") (pinfunction "P0[1]/CAN_TD1/U3_RXD/I2C1_SCL/U0_RXD_N11") (pintype "bidirectional"))
    )
    (net (code "78") (name "/MMC_SDA") (class "Default")
      (node (ref "IC51") (pin "M10") (pinfunction "P0[0]/CAN_RD1/U3_TXD/I2C1_SDA/U0_TXD_M10") (pintype "bidirectional"))
    )
    (net (code "79") (name "/MMC_SSEL1") (class "Default")
      (node (ref "IC51") (pin "D11") (pinfunction "P0[6]/I2S_RX_SDA/SSP1_SSEL/T2_MAT0/U1_RTS_D11") (pintype "bidirectional"))
    )
    (net (code "80") (name "/MOD_HANDLE") (class "Default")
      (node (ref "IC51") (pin "B14") (pinfunction "P4[13]/EMC_A[13]_B14") (pintype "bidirectional"))
      (node (ref "PB2") (pin "1") (pinfunction "1_1") (pintype "bidirectional"))
      (node (ref "PB2") (pin "2") (pinfunction "2_2") (pintype "bidirectional"))
      (node (ref "R413") (pin "1") (pinfunction "1_1") (pintype "passive"))
    )
    (net (code "81") (name "/P0V95I_PG") (class "Default")
      (node (ref "IC51") (pin "P5") (pinfunction "P1[19]/~{USB_TX_E1}/~{USB_PPWR1}/T1_CAP1/MC_0A/SSP1_SCK/U2_OE_P5") (pintype "bidirectional"))
    )
    (net (code "82") (name "/P0V95_PG") (class "Default")
      (node (ref "IC51") (pin "C9") (pinfunction "P1[17]/ENET_MDIO/I2S_RX_MCLK_C9") (pintype "bidirectional"))
    )
    (net (code "83") (name "/P1") (class "Default")
      (node (ref "IC51") (pin "G5") (pinfunction "P3[3]/EMC_D[3]_G5") (pintype "bidirectional"))
      (node (ref "R390") (pin "2") (pinfunction "2_2") (pintype "passive"))
      (node (ref "R391") (pin "2") (pinfunction "2_2") (pintype "passive"))
      (node (ref "R392") (pin "2") (pinfunction "2_2") (pintype "passive"))
    )
    (net (code "84") (name "/P1V2_PG") (class "Default")
      (node (ref "IC51") (pin "L5") (pinfunction "P1[18]/USB_UP_LED1/PWM1[1]/T1_CAP0/SSP1_MISO_L5") (pintype "bidirectional"))
    )
    (net (code "85") (name "/P2") (class "Default")
      (node (ref "IC51") (pin "D3") (pinfunction "P3[4]/EMC_D[4]_D3") (pintype "bidirectional"))
      (node (ref "R399") (pin "2") (pinfunction "2_2") (pintype "passive"))
    )
    (net (code "86") (name "/P2_BLUE") (class "Default")
      (node (ref "LD20") (pin "1") (pinfunction "C_1") (pintype "passive"))
      (node (ref "R399") (pin "1") (pinfunction "1_1") (pintype "passive"))
    )
    (net (code "87") (name "/P3") (class "Default")
      (node (ref "IC51") (pin "E3") (pinfunction "P3[5]/EMC_D[5]_E3") (pintype "bidirectional"))
      (node (ref "R400") (pin "2") (pinfunction "2_2") (pintype "passive"))
    )
    (net (code "88") (name "/P3V3_FMC_PGOOD") (class "Default")
      (node (ref "IC51") (pin "B10") (pinfunction "P1[6]/ENET_TX_CLK/SD_DAT[0]/PWM0[4]_B10") (pintype "bidirectional"))
    )
    (net (code "89") (name "/P3_GREEN") (class "Default")
      (node (ref "LD18") (pin "1") (pinfunction "C_1") (pintype "passive"))
      (node (ref "R400") (pin "1") (pinfunction "1_1") (pintype "passive"))
    )
    (net (code "90") (name "/P4") (class "Default")
      (node (ref "IC51") (pin "L7") (pinfunction "P1[25]/~{USB_LS1}/~{USB_HSTEN1}/T1_MAT1/MC_1A/CLKOUT_L7") (pintype "bidirectional"))
      (node (ref "R401") (pin "2") (pinfunction "2_2") (pintype "passive"))
    )
    (net (code "91") (name "/P4_RED") (class "Default")
      (node (ref "LD19") (pin "1") (pinfunction "C_1") (pintype "passive"))
      (node (ref "R401") (pin "1") (pinfunction "1_1") (pintype "passive"))
    )
    (net (code "92") (name "/P12V0_OK") (class "Default")
      (node (ref "IC51") (pin "N4") (pinfunction "P0[30]/USB_D-1/~{EINT1}_N4") (pintype "bidirectional"))
    )
    (net (code "93") (name "/PGOOD_P5V0") (class "Default")
      (node (ref "IC51") (pin "M6") (pinfunction "P1[22]/USB_RCV1/USB_PWRD1/T1_MAT0/MC_0B/SSP1_MOSI_M6") (pintype "bidirectional"))
    )
    (net (code "94") (name "/RTM_JTAG_Override") (class "Default")
      (node (ref "IC51") (pin "D9") (pinfunction "P4[25]/~{EMC_WE}_D9") (pintype "bidirectional"))
    )
    (net (code "95") (name "/RTM_PS#") (class "Default")
      (node (ref "D28") (pin "1") (pinfunction "C_1") (pintype "passive"))
      (node (ref "R423") (pin "1") (pinfunction "1_1") (pintype "passive"))
      (node (ref "R424") (pin "1") (pinfunction "1_1") (pintype "passive"))
    )
    (net (code "96") (name "/SDCLK") (class "Default")
      (node (ref "B5") (pin "1") (pinfunction "1_1") (pintype "passive"))
      (node (ref "IC51") (pin "J10") (pinfunction "P0[19]/U1_DSR/SD_CLK/I2C1_SDA_J10") (pintype "bidirectional"))
    )
    (net (code "97") (name "/SDCMD") (class "Default")
      (node (ref "B6") (pin "1") (pinfunction "1_1") (pintype "passive"))
      (node (ref "IC51") (pin "K14") (pinfunction "P0[20]/U1_DTR/SD_CMD/I2C1_SCL_K14") (pintype "bidirectional"))
    )
    (net (code "98") (name "/SDDAT0") (class "Default")
      (node (ref "B8") (pin "1") (pinfunction "1_1") (pintype "passive"))
      (node (ref "IC51") (pin "L14") (pinfunction "P0[22]/U1_RTS/SD_DAT[0]/U4_TXD/CAN_TD1_L14") (pintype "bidirectional"))
    )
    (net (code "99") (name "/SDDAT1") (class "Default")
      (node (ref "B9") (pin "1") (pinfunction "1_1") (pintype "passive"))
      (node (ref "IC51") (pin "M12") (pinfunction "P2[11]/~{EINT1}/SD_DAT[1]/I2S_TX_SCK_M12") (pintype "bidirectional"))
    )
    (net (code "100") (name "/SDDAT2") (class "Default")
      (node (ref "B10") (pin "1") (pinfunction "1_1") (pintype "passive"))
      (node (ref "IC51") (pin "N14") (pinfunction "P2[12]/~{EINT2}/SD_DAT[2]/I2S_TX_WS_N14") (pintype "bidirectional"))
    )
    (net (code "101") (name "/SDDAT3") (class "Default")
      (node (ref "B11") (pin "1") (pinfunction "1_1") (pintype "passive"))
      (node (ref "IC51") (pin "M11") (pinfunction "P2[13]/~{EINT3}/SD_DAT[3]/I2S_TX_SDA_M11") (pintype "bidirectional"))
    )
    (net (code "102") (name "/SDPWR") (class "Default")
      (node (ref "B7") (pin "1") (pinfunction "1_1") (pintype "passive"))
      (node (ref "IC51") (pin "K11") (pinfunction "P0[21]/U1_RI/SD_PWR/U4_OE/CAN_RD1/U4_SCLK_K11") (pintype "bidirectional"))
    )
    (net (code "103") (name "/SDRAM_PGOOD") (class "Default")
      (node (ref "IC51") (pin "E14") (pinfunction "P2[4]/PWM1[5]/U1_DSR/T2_MAT1/TRACEDATA[1]_E14") (pintype "bidirectional"))
    )
    (net (code "104") (name "/SSP0_MISO") (class "Default")
      (node (ref "IC2") (pin "8") (pinfunction "DQ1_8") (pintype "bidirectional"))
      (node (ref "IC51") (pin "J12") (pinfunction "P0[17]/U1_CTS/SSP0_MISO_J12") (pintype "bidirectional"))
    )
    (net (code "105") (name "/SSP0_MOSI") (class "Default")
      (node (ref "IC2") (pin "15") (pinfunction "DQ0_15") (pintype "bidirectional"))
      (node (ref "IC51") (pin "J13") (pinfunction "P0[18]/U1_DCD/SSP0_MOSI_J13") (pintype "bidirectional"))
    )
    (net (code "106") (name "/SSP0_SCK") (class "Default")
      (node (ref "IC2") (pin "16") (pinfunction "C_16") (pintype "input"))
      (node (ref "IC51") (pin "H13") (pinfunction "P0[15]/U1_TXD/SSP0_SCK_H13") (pintype "bidirectional"))
    )
    (net (code "107") (name "/SSP0_SSEL") (class "Default")
      (node (ref "IC2") (pin "7") (pinfunction "~{S}_7") (pintype "input"))
      (node (ref "IC51") (pin "H14") (pinfunction "P0[16]/U1_RXD/SSP0_SSEL_H14") (pintype "bidirectional"))
    )
    (net (code "108") (name "/SW") (class "Default")
      (node (ref "IC51") (pin "F10") (pinfunction "P4[12]/EMC_A[12]_F10") (pintype "bidirectional"))
      (node (ref "PB1") (pin "2") (pinfunction "2_2") (pintype "bidirectional"))
      (node (ref "R412") (pin "1") (pinfunction "1_1") (pintype "passive"))
    )
    (net (code "112") (name "/{I2C}") (class "Default")
      (node (ref "IC51") (pin "A13") (pinfunction "P0[9]/I2S_TX_SDA/SSP1_MOSI/T2_MAT3/RTC_EV2_A13") (pintype "bidirectional"))
    )
    (net (code "117") (name "GND") (class "Default")
      (node (ref "C2") (pin "1") (pinfunction "1_1") (pintype "passive"))
      (node (ref "D23") (pin "2") (pinfunction "A_2") (pintype "passive"))
      (node (ref "D24") (pin "2") (pinfunction "A_2") (pintype "passive"))
      (node (ref "D25") (pin "2") (pinfunction "A_2") (pintype "passive"))
      (node (ref "D26") (pin "2") (pinfunction "A_2") (pintype "passive"))
      (node (ref "D27") (pin "2") (pinfunction "A_2") (pintype "passive"))
      (node (ref "D28") (pin "2") (pinfunction "A_2") (pintype "passive"))
      (node (ref "IC2") (pin "10") (pinfunction "VSS_10") (pintype "power_in"))
      (node (ref "PB1") (pin "1") (pinfunction "1_1") (pintype "bidirectional"))
      (node (ref "PB1") (pin "3") (pinfunction "3_3") (pintype "passive"))
      (node (ref "PB1") (pin "4") (pinfunction "4_4") (pintype "passive"))
      (node (ref "PB2") (pin "3") (pinfunction "3_3") (pintype "bidirectional"))
      (node (ref "PB2") (pin "4") (pinfunction "4_4") (pintype "bidirectional"))
      (node (ref "R415") (pin "1") (pinfunction "1_1") (pintype "passive"))
      (node (ref "R416") (pin "1") (pinfunction "1_1") (pintype "passive"))
      (node (ref "R417") (pin "1") (pinfunction "1_1") (pintype "passive"))
      (node (ref "R422") (pin "1") (pinfunction "1_1") (pintype "passive"))
      (node (ref "R436") (pin "1") (pinfunction "1_1") (pintype "passive"))
    )
    (net (code "118") (name "Net-(IC2-~{HOLD}{slash}DQ3)") (class "Default")
      (node (ref "IC2") (pin "1") (pinfunction "~{HOLD}/DQ3_1") (pintype "bidirectional"))
      (node (ref "R18") (pin "1") (pinfunction "1_1") (pintype "passive"))
    )
    (net (code "119") (name "Net-(IC2-~{RESET})") (class "Default")
      (node (ref "IC2") (pin "3") (pinfunction "~{RESET}_3") (pintype "input"))
      (node (ref "R203") (pin "1") (pinfunction "1_1") (pintype "passive"))
    )
    (net (code "120") (name "Net-(IC2-~{W}{slash}DQ2)") (class "Default")
      (node (ref "IC2") (pin "9") (pinfunction "~{W}/DQ2_9") (pintype "bidirectional"))
      (node (ref "R17") (pin "1") (pinfunction "1_1") (pintype "passive"))
    )
    (net (code "121") (name "Net-(IC51A-P0[10]{slash}U2_TXD{slash}I2C2_SDA{slash}T3_MAT0)") (class "Default")
      (node (ref "IC51") (pin "L10") (pinfunction "P0[10]/U2_TXD/I2C2_SDA/T3_MAT0_L10") (pintype "bidirectional"))
      (node (ref "R427") (pin "2") (pinfunction "2_2") (pintype "passive"))
    )
    (net (code "122") (name "Net-(IC51A-P0[11]{slash}U2_RXD{slash}I2C2_SCL{slash}T3_MAT1)") (class "Default")
      (node (ref "IC51") (pin "P12") (pinfunction "P0[11]/U2_RXD/I2C2_SCL/T3_MAT1_P12") (pintype "bidirectional"))
      (node (ref "R426") (pin "2") (pinfunction "2_2") (pintype "passive"))
    )
    (net (code "123") (name "Net-(IC51A-P0[29]{slash}USB_D+1{slash}~{EINT0})") (class "Default")
      (node (ref "IC51") (pin "K5") (pinfunction "P0[29]/USB_D+1/~{EINT0}_K5") (pintype "bidirectional"))
      (node (ref "R424") (pin "2") (pinfunction "2_2") (pintype "passive"))
    )
    (net (code "124") (name "Net-(IC51B-P3[7]{slash}EMC_D[7])") (class "Default")
      (node (ref "IC51") (pin "G3") (pinfunction "P3[7]/EMC_D[7]_G3") (pintype "bidirectional"))
      (node (ref "R428") (pin "2") (pinfunction "2_2") (pintype "passive"))
    )
    (net (code "125") (name "Net-(IC51B-P3[9]{slash}EMC_D[9])") (class "Default")
      (node (ref "IC51") (pin "A4") (pinfunction "P3[9]/EMC_D[9]_A4") (pintype "bidirectional"))
      (node (ref "R429") (pin "2") (pinfunction "2_2") (pintype "passive"))
    )
    (net (code "126") (name "Net-(IC51B-P3[11]{slash}EMC_D[11])") (class "Default")
      (node (ref "IC51") (pin "B2") (pinfunction "P3[11]/EMC_D[11]_B2") (pintype "bidirectional"))
      (node (ref "R432") (pin "2") (pinfunction "2_2") (pintype "passive"))
    )
    (net (code "127") (name "Net-(IC51B-P3[12]{slash}EMC_D[12])") (class "Default")
      (node (ref "IC51") (pin "A1") (pinfunction "P3[12]/EMC_D[12]_A1") (pintype "bidirectional"))
      (node (ref "R439") (pin "2") (pinfunction "2_2") (pintype "passive"))
    )
    (net (code "128") (name "Net-(IC51B-P3[13]{slash}EMC_D[13])") (class "Default")
      (node (ref "IC51") (pin "C1") (pinfunction "P3[13]/EMC_D[13]_C1") (pintype "bidirectional"))
      (node (ref "R440") (pin "2") (pinfunction "2_2") (pintype "passive"))
    )
    (net (code "129") (name "P3V3MP") (class "Default")
      (node (ref "C2") (pin "2") (pinfunction "2_2") (pintype "passive"))
      (node (ref "IC2") (pin "2") (pinfunction "VCC_2") (pintype "power_in"))
      (node (ref "LD18") (pin "2") (pinfunction "A_2") (pintype "passive"))
      (node (ref "LD19") (pin "2") (pinfunction "A_2") (pintype "passive"))
      (node (ref "LD20") (pin "2") (pinfunction "A_2") (pintype "passive"))
      (node (ref "R17") (pin "2") (pinfunction "2_2") (pintype "passive"))
      (node (ref "R18") (pin "2") (pinfunction "2_2") (pintype "passive"))
      (node (ref "R203") (pin "2") (pinfunction "2_2") (pintype "passive"))
      (node (ref "R402") (pin "1") (pinfunction "1_1") (pintype "passive"))
      (node (ref "R403") (pin "1") (pinfunction "1_1") (pintype "passive"))
      (node (ref "R405") (pin "2") (pinfunction "2_2") (pintype "passive"))
      (node (ref "R406") (pin "2") (pinfunction "2_2") (pintype "passive"))
      (node (ref "R407") (pin "2") (pinfunction "2_2") (pintype "passive"))
      (node (ref "R412") (pin "2") (pinfunction "2_2") (pintype "passive"))
      (node (ref "R413") (pin "2") (pinfunction "2_2") (pintype "passive"))
      (node (ref "R414") (pin "2") (pinfunction "2_2") (pintype "passive"))
      (node (ref "R418") (pin "1") (pinfunction "1_1") (pintype "passive"))
      (node (ref "R419") (pin "1") (pinfunction "1_1") (pintype "passive"))
      (node (ref "R420") (pin "1") (pinfunction "1_1") (pintype "passive"))
      (node (ref "R421") (pin "1") (pinfunction "1_1") (pintype "passive"))
      (node (ref "R423") (pin "2") (pinfunction "2_2") (pintype "passive"))
      (node (ref "R425") (pin "1") (pinfunction "1_1") (pintype "passive"))
      (node (ref "R430") (pin "2") (pinfunction "2_2") (pintype "passive"))
      (node (ref "R431") (pin "2") (pinfunction "2_2") (pintype "passive"))
      (node (ref "R433") (pin "2") (pinfunction "2_2") (pintype "passive"))
      (node (ref "R437") (pin "2") (pinfunction "2_2") (pintype "passive"))
      (node (ref "R438") (pin "2") (pinfunction "2_2") (pintype "passive"))
    )
    (net (code "130") (name "unconnected-(IC2-DNU-Pad4)") (class "Default")
      (node (ref "IC2") (pin "4") (pinfunction "DNU_4") (pintype "passive"))
    )
    (net (code "131") (name "unconnected-(IC2-DNU-Pad5)") (class "Default")
      (node (ref "IC2") (pin "5") (pinfunction "DNU_5") (pintype "passive"))
    )
    (net (code "132") (name "unconnected-(IC2-DNU-Pad6)") (class "Default")
      (node (ref "IC2") (pin "6") (pinfunction "DNU_6") (pintype "passive"))
    )
    (net (code "133") (name "unconnected-(IC2-DNU-Pad11)") (class "Default")
      (node (ref "IC2") (pin "11") (pinfunction "DNU_11") (pintype "passive"))
    )
    (net (code "134") (name "unconnected-(IC2-DNU-Pad12)") (class "Default")
      (node (ref "IC2") (pin "12") (pinfunction "DNU_12") (pintype "passive"))
    )
    (net (code "135") (name "unconnected-(IC2-DNU-Pad13)") (class "Default")
      (node (ref "IC2") (pin "13") (pinfunction "DNU_13") (pintype "passive"))
    )
    (net (code "136") (name "unconnected-(IC2-DNU-Pad14)") (class "Default")
      (node (ref "IC2") (pin "14") (pinfunction "DNU_14") (pintype "passive"))
    )
    (net (code "137") (name "unconnected-(IC51A-P0[23]{slash}ADC0_IN[0]{slash}I2S_RX_SCK{slash}T3_CAP0-PadF5)") (class "Default")
      (node (ref "IC51") (pin "F5") (pinfunction "P0[23]/ADC0_IN[0]/I2S_RX_SCK/T3_CAP0_F5") (pintype "bidirectional"))
    )
    (net (code "138") (name "unconnected-(IC51A-P0[24]{slash}ADC0_IN[1]{slash}I2S_RX_WS{slash}T3_CAP1-PadE1)") (class "Default")
      (node (ref "IC51") (pin "E1") (pinfunction "P0[24]/ADC0_IN[1]/I2S_RX_WS/T3_CAP1_E1") (pintype "bidirectional+no_connect"))
    )
    (net (code "139") (name "unconnected-(IC51A-P0[25]{slash}ADC0_IN[2]{slash}I2S_RX_SDA{slash}U3_TXD-PadE4)") (class "Default")
      (node (ref "IC51") (pin "E4") (pinfunction "P0[25]/ADC0_IN[2]/I2S_RX_SDA/U3_TXD_E4") (pintype "bidirectional+no_connect"))
    )
    (net (code "140") (name "unconnected-(IC51A-P0[26]{slash}ADC0_IN[3]{slash}DAC_OUT{slash}U3_RXD-PadD1)") (class "Default")
      (node (ref "IC51") (pin "D1") (pinfunction "P0[26]/ADC0_IN[3]/DAC_OUT/U3_RXD_D1") (pintype "bidirectional+no_connect"))
    )
    (net (code "141") (name "unconnected-(IC51A-P0[31]{slash}USB_D+2-PadN1)") (class "Default")
      (node (ref "IC51") (pin "N1") (pinfunction "P0[31]/USB_D+2_N1") (pintype "bidirectional"))
    )
    (net (code "142") (name "unconnected-(IC51A-P1[0]{slash}ENET_TXD0{slash}T3_CAP1{slash}SSP2_SCK-PadB5)") (class "Default")
      (node (ref "IC51") (pin "B5") (pinfunction "P1[0]/ENET_TXD0/T3_CAP1/SSP2_SCK_B5") (pintype "bidirectional+no_connect"))
    )
    (net (code "143") (name "unconnected-(IC51A-P1[1]{slash}ENET_TXD1{slash}T3_MAT3{slash}SSP2_MOSI-PadA5)") (class "Default")
      (node (ref "IC51") (pin "A5") (pinfunction "P1[1]/ENET_TXD1/T3_MAT3/SSP2_MOSI_A5") (pintype "bidirectional+no_connect"))
    )
    (net (code "144") (name "unconnected-(IC51A-P1[2]{slash}ENET_TXD2{slash}SD_CLK{slash}PWM0[1]-PadB7)") (class "Default")
      (node (ref "IC51") (pin "B7") (pinfunction "P1[2]/ENET_TXD2/SD_CLK/PWM0[1]_B7") (pintype "bidirectional+no_connect"))
    )
    (net (code "145") (name "unconnected-(IC51A-P1[3]{slash}ENET_TXD3{slash}SD_CMD{slash}PWM0[2]-PadA9)") (class "Default")
      (node (ref "IC51") (pin "A9") (pinfunction "P1[3]/ENET_TXD3/SD_CMD/PWM0[2]_A9") (pintype "bidirectional+no_connect"))
    )
    (net (code "146") (name "unconnected-(IC51A-P1[4]{slash}ENET_TX_EN{slash}T3_MAT2{slash}SSP2_MISO-PadC6)") (class "Default")
      (node (ref "IC51") (pin "C6") (pinfunction "P1[4]/ENET_TX_EN/T3_MAT2/SSP2_MISO_C6") (pintype "bidirectional+no_connect"))
    )
    (net (code "147") (name "unconnected-(IC51A-P1[5]{slash}ENET_TX_ER{slash}SD_PWR{slash}PWM0[3]-PadB13)") (class "Default")
      (node (ref "IC51") (pin "B13") (pinfunction "P1[5]/ENET_TX_ER/SD_PWR/PWM0[3]_B13") (pintype "bidirectional+no_connect"))
    )
    (net (code "148") (name "unconnected-(IC51A-P1[9]{slash}ENET_RXD0{slash}T3_MAT0-PadD7)") (class "Default")
      (node (ref "IC51") (pin "D7") (pinfunction "P1[9]/ENET_RXD0/T3_MAT0_D7") (pintype "bidirectional"))
    )
    (net (code "149") (name "unconnected-(IC51B-P2[0]{slash}PWM1[1]{slash}U1_TXD-PadD12)") (class "Default")
      (node (ref "IC51") (pin "D12") (pinfunction "P2[0]/PWM1[1]/U1_TXD_D12") (pintype "bidirectional+no_connect"))
    )
    (net (code "150") (name "unconnected-(IC51B-P2[1]{slash}PWM1[2]{slash}U1_RXD-PadC14)") (class "Default")
      (node (ref "IC51") (pin "C14") (pinfunction "P2[1]/PWM1[2]/U1_RXD_C14") (pintype "bidirectional+no_connect"))
    )
    (net (code "151") (name "unconnected-(IC51B-P2[2]{slash}PWM1[3]{slash}U1_CTS{slash}T2_MAT3{slash}TRACEDATA[3]-PadE11)") (class "Default")
      (node (ref "IC51") (pin "E11") (pinfunction "P2[2]/PWM1[3]/U1_CTS/T2_MAT3/TRACEDATA[3]_E11") (pintype "bidirectional+no_connect"))
    )
    (net (code "152") (name "unconnected-(IC51B-P2[3]{slash}PWM1[4]{slash}U1_DCD{slash}T2_MAT2{slash}TRACEDATA[2]-PadE13)") (class "Default")
      (node (ref "IC51") (pin "E13") (pinfunction "P2[3]/PWM1[4]/U1_DCD/T2_MAT2/TRACEDATA[2]_E13") (pintype "bidirectional+no_connect"))
    )
    (net (code "153") (name "unconnected-(IC51B-P2[5]{slash}PWM1[6]{slash}U1_DTR{slash}T2_MAT0{slash}TRACEDATA[0]-PadF12)") (class "Default")
      (node (ref "IC51") (pin "F12") (pinfunction "P2[5]/PWM1[6]/U1_DTR/T2_MAT0/TRACEDATA[0]_F12") (pintype "bidirectional+no_connect"))
    )
    (net (code "154") (name "unconnected-(IC51B-P2[6]{slash}PWM1_CAP0{slash}U1_RI{slash}T2_CAP0{slash}U2_OE{slash}TRACECLK-PadF13)") (class "Default")
      (node (ref "IC51") (pin "F13") (pinfunction "P2[6]/PWM1_CAP0/U1_RI/T2_CAP0/U2_OE/TRACECLK_F13") (pintype "bidirectional+no_connect"))
    )
    (net (code "155") (name "unconnected-(IC51B-P2[7]{slash}CAN_RD2{slash}U1_RTS-PadG11)") (class "Default")
      (node (ref "IC51") (pin "G11") (pinfunction "P2[7]/CAN_RD2/U1_RTS_G11") (pintype "bidirectional+no_connect"))
    )
    (net (code "156") (name "unconnected-(IC51B-P2[8]{slash}CAN_TD2{slash}U2_TXD{slash}U1_CTS{slash}ENET_MDC-PadG14)") (class "Default")
      (node (ref "IC51") (pin "G14") (pinfunction "P2[8]/CAN_TD2/U2_TXD/U1_CTS/ENET_MDC_G14") (pintype "bidirectional+no_connect"))
    )
    (net (code "157") (name "unconnected-(IC51B-P2[9]{slash}USB_CONNECT1{slash}U2_RXD{slash}U4_RXD{slash}ENET_MDIO-PadH11)") (class "Default")
      (node (ref "IC51") (pin "H11") (pinfunction "P2[9]/USB_CONNECT1/U2_RXD/U4_RXD/ENET_MDIO_H11") (pintype "bidirectional+no_connect"))
    )
    (net (code "158") (name "unconnected-(IC51B-P2[20]{slash}~{EMC_DYCS0}-PadP6)") (class "Default")
      (node (ref "IC51") (pin "P6") (pinfunction "P2[20]/~{EMC_DYCS0}_P6") (pintype "bidirectional+no_connect"))
    )
    (net (code "159") (name "unconnected-(IC51B-P2[21]{slash}~{EMC_DYCS1}-PadN8)") (class "Default")
      (node (ref "IC51") (pin "N8") (pinfunction "P2[21]/~{EMC_DYCS1}_N8") (pintype "bidirectional+no_connect"))
    )
    (net (code "160") (name "unconnected-(IC51B-P2[24]{slash}EMC_CKE0-PadP1)") (class "Default")
      (node (ref "IC51") (pin "P1") (pinfunction "P2[24]/EMC_CKE0_P1") (pintype "bidirectional+no_connect"))
    )
    (net (code "161") (name "unconnected-(IC51B-P2[25]{slash}EMC_CKE1-PadP2)") (class "Default")
      (node (ref "IC51") (pin "P2") (pinfunction "P2[25]/EMC_CKE1_P2") (pintype "bidirectional+no_connect"))
    )
    (net (code "162") (name "unconnected-(IC51B-P3[14]{slash}EMC_D[14]-PadF1)") (class "Default")
      (node (ref "IC51") (pin "F1") (pinfunction "P3[14]/EMC_D[14]_F1") (pintype "bidirectional+no_connect"))
    )
    (net (code "163") (name "unconnected-(IC51B-P3[15]{slash}EMC_D[15]-PadG4)") (class "Default")
      (node (ref "IC51") (pin "G4") (pinfunction "P3[15]/EMC_D[15]_G4") (pintype "bidirectional+no_connect"))
    )
    (net (code "164") (name "unconnected-(IC51C-P4[0]{slash}EMC_A[0]-PadL6)") (class "Default")
      (node (ref "IC51") (pin "L6") (pinfunction "P4[0]/EMC_A[0]_L6") (pintype "bidirectional+no_connect"))
    )
    (net (code "165") (name "unconnected-(IC51C-P4[1]{slash}EMC_A[1]-PadM7)") (class "Default")
      (node (ref "IC51") (pin "M7") (pinfunction "P4[1]/EMC_A[1]_M7") (pintype "bidirectional+no_connect"))
    )
    (net (code "166") (name "unconnected-(IC51C-P4[2]{slash}EMC_A[2]-PadM8)") (class "Default")
      (node (ref "IC51") (pin "M8") (pinfunction "P4[2]/EMC_A[2]_M8") (pintype "bidirectional+no_connect"))
    )
    (net (code "167") (name "unconnected-(IC51C-P4[3]{slash}EMC_A[3]-PadK9)") (class "Default")
      (node (ref "IC51") (pin "K9") (pinfunction "P4[3]/EMC_A[3]_K9") (pintype "bidirectional+no_connect"))
    )
    (net (code "168") (name "unconnected-(IC51C-P4[4]{slash}EMC_A[4]-PadP13)") (class "Default")
      (node (ref "IC51") (pin "P13") (pinfunction "P4[4]/EMC_A[4]_P13") (pintype "bidirectional+no_connect"))
    )
    (net (code "169") (name "unconnected-(IC51C-P4[5]{slash}EMC_A[5]-PadH10)") (class "Default")
      (node (ref "IC51") (pin "H10") (pinfunction "P4[5]/EMC_A[5]_H10") (pintype "bidirectional+no_connect"))
    )
    (net (code "170") (name "unconnected-(IC51C-P4[6]{slash}EMC_A[6]-PadK10)") (class "Default")
      (node (ref "IC51") (pin "K10") (pinfunction "P4[6]/EMC_A[6]_K10") (pintype "bidirectional+no_connect"))
    )
    (net (code "171") (name "unconnected-(IC51C-P4[7]{slash}EMC_A[7]-PadK12)") (class "Default")
      (node (ref "IC51") (pin "K12") (pinfunction "P4[7]/EMC_A[7]_K12") (pintype "bidirectional+no_connect"))
    )
    (net (code "172") (name "unconnected-(IC51C-P4[10]{slash}EMC_A[10]-PadG12)") (class "Default")
      (node (ref "IC51") (pin "G12") (pinfunction "P4[10]/EMC_A[10]_G12") (pintype "bidirectional+no_connect"))
    )
    (net (code "173") (name "unconnected-(IC51C-P4[14]{slash}EMC_A[14]-PadE8)") (class "Default")
      (node (ref "IC51") (pin "E8") (pinfunction "P4[14]/EMC_A[14]_E8") (pintype "bidirectional+no_connect"))
    )
    (net (code "174") (name "unconnected-(IC51C-P4[15]{slash}EMC_A[15]-PadC10)") (class "Default")
      (node (ref "IC51") (pin "C10") (pinfunction "P4[15]/EMC_A[15]_C10") (pintype "bidirectional+no_connect"))
    )
    (net (code "175") (name "unconnected-(IC51C-P4[16]{slash}EMC_A[16]-PadN12)") (class "Default")
      (node (ref "IC51") (pin "N12") (pinfunction "P4[16]/EMC_A[16]_N12") (pintype "bidirectional+no_connect"))
    )
    (net (code "176") (name "unconnected-(IC51C-P4[17]{slash}EMC_A[17]-PadN13)") (class "Default")
      (node (ref "IC51") (pin "N13") (pinfunction "P4[17]/EMC_A[17]_N13") (pintype "bidirectional+no_connect"))
    )
    (net (code "177") (name "unconnected-(IC51C-P4[18]{slash}EMC_A[18]-PadP14)") (class "Default")
      (node (ref "IC51") (pin "P14") (pinfunction "P4[18]/EMC_A[18]_P14") (pintype "bidirectional+no_connect"))
    )
    (net (code "178") (name "unconnected-(IC51C-P4[19]{slash}EMC_A[19]-PadM14)") (class "Default")
      (node (ref "IC51") (pin "M14") (pinfunction "P4[19]/EMC_A[19]_M14") (pintype "bidirectional+no_connect"))
    )
    (net (code "179") (name "unconnected-(IC51C-P4[24]{slash}~{EMC_OE}-PadC8)") (class "Default")
      (node (ref "IC51") (pin "C8") (pinfunction "P4[24]/~{EMC_OE}_C8") (pintype "bidirectional+no_connect"))
    )
    (net (code "180") (name "unconnected-(IC51C-P4[27]{slash}~{EMC_BLS1}-PadF14)") (class "Default")
      (node (ref "IC51") (pin "F14") (pinfunction "P4[27]/~{EMC_BLS1}_F14") (pintype "bidirectional+no_connect"))
    )
    (net (code "181") (name "unconnected-(IC51C-P4[28]{slash}~{EMC_BLS2}{slash}U3_TXD{slash}T2_MAT0-PadD10)") (class "Default")
      (node (ref "IC51") (pin "D10") (pinfunction "P4[28]/~{EMC_BLS2}/U3_TXD/T2_MAT0_D10") (pintype "bidirectional+no_connect"))
    )
    (net (code "182") (name "unconnected-(IC51C-P4[29]{slash}~{EMC_BLS3}{slash}U3_RXD{slash}T2_MAT1{slash}I2C2_SCL-PadB9)") (class "Default")
      (node (ref "IC51") (pin "B9") (pinfunction "P4[29]/~{EMC_BLS3}/U3_RXD/T2_MAT1/I2C2_SCL_B9") (pintype "bidirectional+no_connect"))
    )
    (net (code "183") (name "unconnected-(IC51C-P4[30]{slash}~{EMC_CS0}-PadC7)") (class "Default")
      (node (ref "IC51") (pin "C7") (pinfunction "P4[30]/~{EMC_CS0}_C7") (pintype "bidirectional+no_connect"))
    )
    (net (code "184") (name "unconnected-(IC51C-P4[31]{slash}~{EMC_CS1}-PadE7)") (class "Default")
      (node (ref "IC51") (pin "E7") (pinfunction "P4[31]/~{EMC_CS1}_E7") (pintype "bidirectional+no_connect"))
    )
    (net (code "185") (name "unconnected-(IC51C-P5[1]{slash}EMC_A[25]{slash}SSP2_MISO{slash}T2_MAT3-PadH1)") (class "Default")
      (node (ref "IC51") (pin "H1") (pinfunction "P5[1]/EMC_A[25]/SSP2_MISO/T2_MAT3_H1") (pintype "bidirectional+no_connect"))
    )
    (net (code "186") (name "unconnected-(IC51C-P5[2]{slash}T3_MAT2{slash}I2C0_SDA-PadL12)") (class "Default")
      (node (ref "IC51") (pin "L12") (pinfunction "P5[2]/T3_MAT2/I2C0_SDA_L12") (pintype "bidirectional+no_connect"))
    )
    (net (code "187") (name "unconnected-(IC51C-P5[3]{slash}U4_RXD{slash}I2C0_SCL-PadG10)") (class "Default")
      (node (ref "IC51") (pin "G10") (pinfunction "P5[3]/U4_RXD/I2C0_SCL_G10") (pintype "bidirectional+no_connect"))
    )
    (net (code "188") (name "unconnected-(IC51C-P5[4]{slash}U0_OE{slash}T3_MAT3{slash}U4_TXD-PadC4)") (class "Default")
      (node (ref "IC51") (pin "C4") (pinfunction "P5[4]/U0_OE/T3_MAT3/U4_TXD_C4") (pintype "bidirectional+no_connect"))
    )
  )
)
